# Error_Generator.net
KiCad netlist of a schematic drawn in Altium Designer
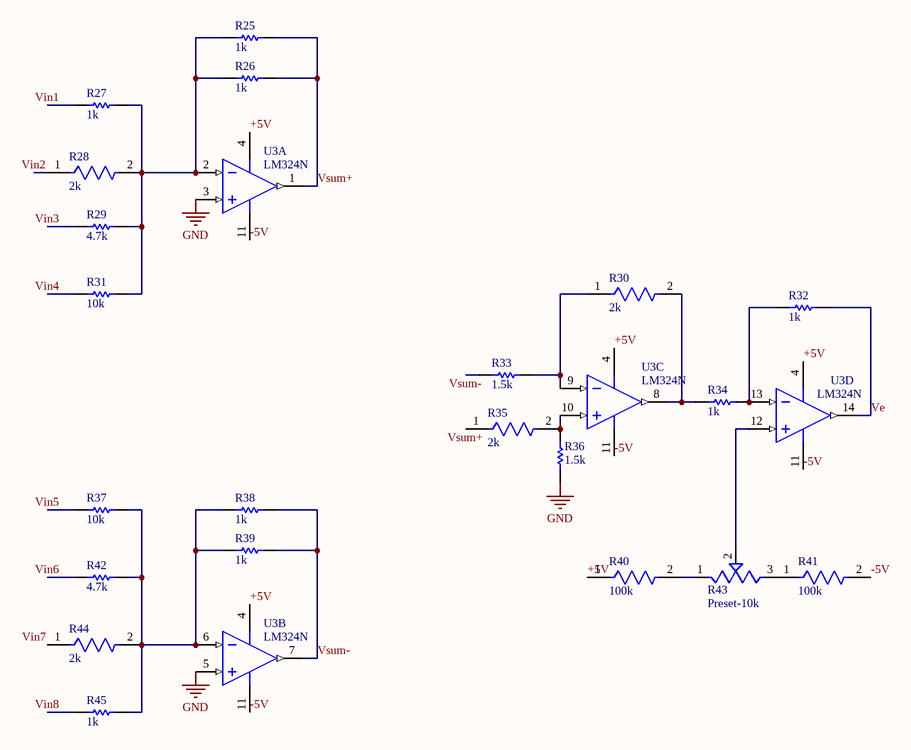
[diagram p0: Error_Generator.SchDoc]

(export (version "E")
  (design (tool "Eeschema 10.0.6"))
  (components
    (comp (ref "R25")
      (value "1k")
      (footprint "RESC2013X60X35ML10T20")
      (fields (field (name "TOLERANCE") "1%") (field (name "MANUFACTURER") "Yageo"))
      (libsource (lib "Resistors") (part "1k"))
    )
    (comp (ref "R26")
      (value "1k")
      (footprint "RESC2013X60X35ML10T20")
      (fields (field (name "TOLERANCE") "1%") (field (name "MANUFACTURER") "Yageo"))
      (libsource (lib "Resistors") (part "1k"))
    )
    (comp (ref "R27")
      (value "1k")
      (footprint "RESC2013X60X35ML10T20")
      (fields (field (name "TOLERANCE") "1%") (field (name "MANUFACTURER") "Yageo"))
      (libsource (lib "Resistors") (part "1k"))
    )
    (comp (ref "R28")
      (value "2k")
      (footprint "FP-CRCW0805-e3-IPC_B")
      (description "RES Thick Film, 2kΩ, 1%, 0.125W, 100ppm/°C, 0805; CRCW08052K00FKEA")
      (fields (field (name "TOLERANCE") "1%"))
      (libsource (lib "Resistors") (part "2k"))
    )
    (comp (ref "R29")
      (value "4.7k")
      (footprint "YAGO-RC0805_M")
      (fields
        (field (name "TOLERANCE") "+/- 1%")
        (field (name "PARTNUMBER") "RC0805FR-074K7L")
        (field (name "POWER") "0.125 W")
      )
      (libsource (lib "Resistors") (part "4.7k"))
    )
    (comp (ref "R30")
      (value "2k")
      (footprint "FP-CRCW0805-e3-IPC_B")
      (description "RES Thick Film, 2kΩ, 1%, 0.125W, 100ppm/°C, 0805; CRCW08052K00FKEA")
      (fields (field (name "TOLERANCE") "1%"))
      (libsource (lib "Resistors") (part "2k"))
    )
    (comp (ref "R31")
      (value "10k")
      (footprint "RESC2013X60X35NL10T20")
      (fields (field (name "MANUFACTURER") "Yageo"))
      (libsource (lib "Resistors") (part "10k"))
    )
    (comp (ref "R32")
      (value "1k")
      (footprint "RESC2013X60X35ML10T20")
      (fields (field (name "TOLERANCE") "1%") (field (name "MANUFACTURER") "Yageo"))
      (libsource (lib "Resistors") (part "1k"))
    )
    (comp (ref "R33")
      (value "1.5k")
      (footprint "RESC2013X60X35LL10T20")
      (description "RES 1.50K OHM 1/8W 1% 0805 SMD; RC0805FR-071K5L")
      (fields (field (name "MANUFACTURER") "Yageo") (field (name "PARTNUMBER") "RC0805FR-071K5L"))
      (libsource (lib "Resistors") (part "1.5k"))
    )
    (comp (ref "R34")
      (value "1k")
      (footprint "RESC2013X60X35ML10T20")
      (fields (field (name "TOLERANCE") "1%") (field (name "MANUFACTURER") "Yageo"))
      (libsource (lib "Resistors") (part "1k"))
    )
    (comp (ref "R35")
      (value "2k")
      (footprint "FP-CRCW0805-e3-IPC_B")
      (description "RES Thick Film, 2kΩ, 1%, 0.125W, 100ppm/°C, 0805; CRCW08052K00FKEA")
      (fields (field (name "TOLERANCE") "1%"))
      (libsource (lib "Resistors") (part "2k"))
    )
    (comp (ref "R36")
      (value "1.5k")
      (footprint "RESC2013X60X35LL10T20")
      (description "RES 1.50K OHM 1/8W 1% 0805 SMD; RC0805FR-071K5L")
      (fields (field (name "MANUFACTURER") "Yageo") (field (name "PARTNUMBER") "RC0805FR-071K5L"))
      (libsource (lib "Resistors") (part "1.5k"))
    )
    (comp (ref "R37")
      (value "10k")
      (footprint "RESC2013X60X35NL10T20")
      (fields (field (name "MANUFACTURER") "Yageo"))
      (libsource (lib "Resistors") (part "10k"))
    )
    (comp (ref "R38")
      (value "1k")
      (footprint "RESC2013X60X35ML10T20")
      (fields (field (name "TOLERANCE") "1%") (field (name "MANUFACTURER") "Yageo"))
      (libsource (lib "Resistors") (part "1k"))
    )
    (comp (ref "R39")
      (value "1k")
      (footprint "RESC2013X60X35ML10T20")
      (fields (field (name "TOLERANCE") "1%") (field (name "MANUFACTURER") "Yageo"))
      (libsource (lib "Resistors") (part "1k"))
    )
    (comp (ref "R40")
      (value "100k")
      (footprint "FP-RC0805-0_6-IPC_C")
      (description "RES 100K OHM 1% 1/8W 0805; RC0805FR-07100KL")
      (fields (field (name "TOLERANCE") "1%"))
      (libsource (lib "Resistors") (part "100k"))
    )
    (comp (ref "R41")
      (value "100k")
      (footprint "FP-RC0805-0_6-IPC_C")
      (description "RES 100K OHM 1% 1/8W 0805; RC0805FR-07100KL")
      (fields (field (name "TOLERANCE") "1%"))
      (libsource (lib "Resistors") (part "100k"))
    )
    (comp (ref "R42")
      (value "4.7k")
      (footprint "YAGO-RC0805_M")
      (fields
        (field (name "TOLERANCE") "+/- 1%")
        (field (name "PARTNUMBER") "RC0805FR-074K7L")
        (field (name "POWER") "0.125 W")
      )
      (libsource (lib "Resistors") (part "4.7k"))
    )
    (comp (ref "R43")
      (value "Preset-10k")
      (footprint "TRIM_3306F-1-103")
      (description "TRIMMER - 6MM ROUND, SINGLE-TURN,CERMET, 10K OHMS ¦ Bourns 3306F-1-103")
      (fields (field (name "MF") "Bourns") (field (name "MP") "3306F-1-103"))
      (libsource (lib "3306F-1-103") (part "Preset"))
    )
    (comp (ref "R44")
      (value "2k")
      (footprint "FP-CRCW0805-e3-IPC_B")
      (description "RES Thick Film, 2kΩ, 1%, 0.125W, 100ppm/°C, 0805; CRCW08052K00FKEA")
      (fields (field (name "TOLERANCE") "1%"))
      (libsource (lib "Resistors") (part "2k"))
    )
    (comp (ref "R45")
      (value "1k")
      (footprint "RESC2013X60X35ML10T20")
      (fields (field (name "TOLERANCE") "1%") (field (name "MANUFACTURER") "Yageo"))
      (libsource (lib "Resistors") (part "1k"))
    )
    (comp (ref "U3")
      (value "LM324N")
      (footprint "N0014A")
      (description "Low Power Quad Operational Amplifier, 14-pin MDIP")
      (fields (field (name "MANUFACTURER") "Texas Instruments"))
      (libsource (lib "ICs") (part "LM324N"))
    )
  )
  (nets
    (net (code "1") (name "/+5V") (class "Default")
      (node (ref "R40") (pin "1") (pinfunction "1_1") (pintype "passive"))
      (node (ref "U3") (pin "4") (pinfunction "V+_4") (pintype "power_in"))
    )
    (net (code "2") (name "/-5V") (class "Default")
      (node (ref "R41") (pin "2") (pinfunction "2_2") (pintype "passive"))
      (node (ref "U3") (pin "11") (pinfunction "GND_11") (pintype "power_in"))
    )
    (net (code "3") (name "/Ve") (class "Default")
      (node (ref "R32") (pin "2") (pinfunction "2_2") (pintype "passive"))
      (node (ref "U3") (pin "14") (pinfunction "OUT4_14") (pintype "output"))
    )
    (net (code "4") (name "/Vin1") (class "Default")
      (node (ref "R27") (pin "1") (pinfunction "1_1") (pintype "passive"))
    )
    (net (code "5") (name "/Vin2") (class "Default")
      (node (ref "R28") (pin "1") (pinfunction "1_1") (pintype "passive"))
    )
    (net (code "6") (name "/Vin3") (class "Default")
      (node (ref "R29") (pin "1") (pinfunction "1_1") (pintype "passive"))
    )
    (net (code "7") (name "/Vin4") (class "Default")
      (node (ref "R31") (pin "1") (pinfunction "1_1") (pintype "passive"))
    )
    (net (code "8") (name "/Vin5") (class "Default")
      (node (ref "R37") (pin "1") (pinfunction "1_1") (pintype "passive"))
    )
    (net (code "9") (name "/Vin6") (class "Default")
      (node (ref "R42") (pin "1") (pinfunction "1_1") (pintype "passive"))
    )
    (net (code "10") (name "/Vin7") (class "Default")
      (node (ref "R44") (pin "1") (pinfunction "1_1") (pintype "passive"))
    )
    (net (code "11") (name "/Vin8") (class "Default")
      (node (ref "R45") (pin "1") (pinfunction "1_1") (pintype "passive"))
    )
    (net (code "12") (name "/Vsum+") (class "Default")
      (node (ref "R25") (pin "2") (pinfunction "2_2") (pintype "passive"))
      (node (ref "R26") (pin "2") (pinfunction "2_2") (pintype "passive"))
      (node (ref "R35") (pin "1") (pinfunction "1_1") (pintype "passive"))
      (node (ref "U3") (pin "1") (pinfunction "OUT1_1") (pintype "output"))
    )
    (net (code "13") (name "/Vsum-") (class "Default")
      (node (ref "R33") (pin "1") (pinfunction "1_1") (pintype "passive"))
      (node (ref "R38") (pin "2") (pinfunction "2_2") (pintype "passive"))
      (node (ref "R39") (pin "2") (pinfunction "2_2") (pintype "passive"))
      (node (ref "U3") (pin "7") (pinfunction "OUT2_7") (pintype "output"))
    )
    (net (code "14") (name "GND") (class "Default")
      (node (ref "R36") (pin "1") (pinfunction "1_1") (pintype "passive"))
      (node (ref "U3") (pin "3") (pinfunction "IN1+_3") (pintype "input"))
      (node (ref "U3") (pin "5") (pinfunction "IN2+_5") (pintype "input"))
    )
    (net (code "15") (name "Net-(R43-CCW)") (class "Default")
      (node (ref "R40") (pin "2") (pinfunction "2_2") (pintype "passive"))
      (node (ref "R43") (pin "1") (pinfunction "CCW_1") (pintype "passive"))
    )
    (net (code "16") (name "Net-(R43-CW)") (class "Default")
      (node (ref "R41") (pin "1") (pinfunction "1_1") (pintype "passive"))
      (node (ref "R43") (pin "3") (pinfunction "CW_3") (pintype "passive"))
    )
    (net (code "17") (name "Net-(R43-W)") (class "Default")
      (node (ref "R43") (pin "2") (pinfunction "W_2") (pintype "passive"))
      (node (ref "U3") (pin "12") (pinfunction "IN4+_12") (pintype "input"))
    )
    (net (code "18") (name "Net-(U3A-IN1-)") (class "Default")
      (node (ref "R25") (pin "1") (pinfunction "1_1") (pintype "passive"))
      (node (ref "R26") (pin "1") (pinfunction "1_1") (pintype "passive"))
      (node (ref "R27") (pin "2") (pinfunction "2_2") (pintype "passive"))
      (node (ref "R28") (pin "2") (pinfunction "2_2") (pintype "passive"))
      (node (ref "R29") (pin "2") (pinfunction "2_2") (pintype "passive"))
      (node (ref "R31") (pin "2") (pinfunction "2_2") (pintype "passive"))
      (node (ref "U3") (pin "2") (pinfunction "IN1-_2") (pintype "input"))
    )
    (net (code "19") (name "Net-(U3B-IN2-)") (class "Default")
      (node (ref "R37") (pin "2") (pinfunction "2_2") (pintype "passive"))
      (node (ref "R38") (pin "1") (pinfunction "1_1") (pintype "passive"))
      (node (ref "R39") (pin "1") (pinfunction "1_1") (pintype "passive"))
      (node (ref "R42") (pin "2") (pinfunction "2_2") (pintype "passive"))
      (node (ref "R44") (pin "2") (pinfunction "2_2") (pintype "passive"))
      (node (ref "R45") (pin "2") (pinfunction "2_2") (pintype "passive"))
      (node (ref "U3") (pin "6") (pinfunction "IN2-_6") (pintype "input"))
    )
    (net (code "20") (name "Net-(U3C-IN3+)") (class "Default")
      (node (ref "R35") (pin "2") (pinfunction "2_2") (pintype "passive"))
      (node (ref "R36") (pin "2") (pinfunction "2_2") (pintype "passive"))
      (node (ref "U3") (pin "10") (pinfunction "IN3+_10") (pintype "input"))
    )
    (net (code "21") (name "Net-(U3C-IN3-)") (class "Default")
      (node (ref "R30") (pin "1") (pinfunction "1_1") (pintype "passive"))
      (node (ref "R33") (pin "2") (pinfunction "2_2") (pintype "passive"))
      (node (ref "U3") (pin "9") (pinfunction "IN3-_9") (pintype "input"))
    )
    (net (code "22") (name "Net-(U3C-OUT3)") (class "Default")
      (node (ref "R30") (pin "2") (pinfunction "2_2") (pintype "passive"))
      (node (ref "R34") (pin "1") (pinfunction "1_1") (pintype "passive"))
      (node (ref "U3") (pin "8") (pinfunction "OUT3_8") (pintype "output"))
    )
    (net (code "23") (name "Net-(U3D-IN4-)") (class "Default")
      (node (ref "R32") (pin "1") (pinfunction "1_1") (pintype "passive"))
      (node (ref "R34") (pin "2") (pinfunction "2_2") (pintype "passive"))
      (node (ref "U3") (pin "13") (pinfunction "IN4-_13") (pintype "input"))
    )
  )
)
